# input_stage.net
KiCad netlist of a schematic drawn in EAGLE
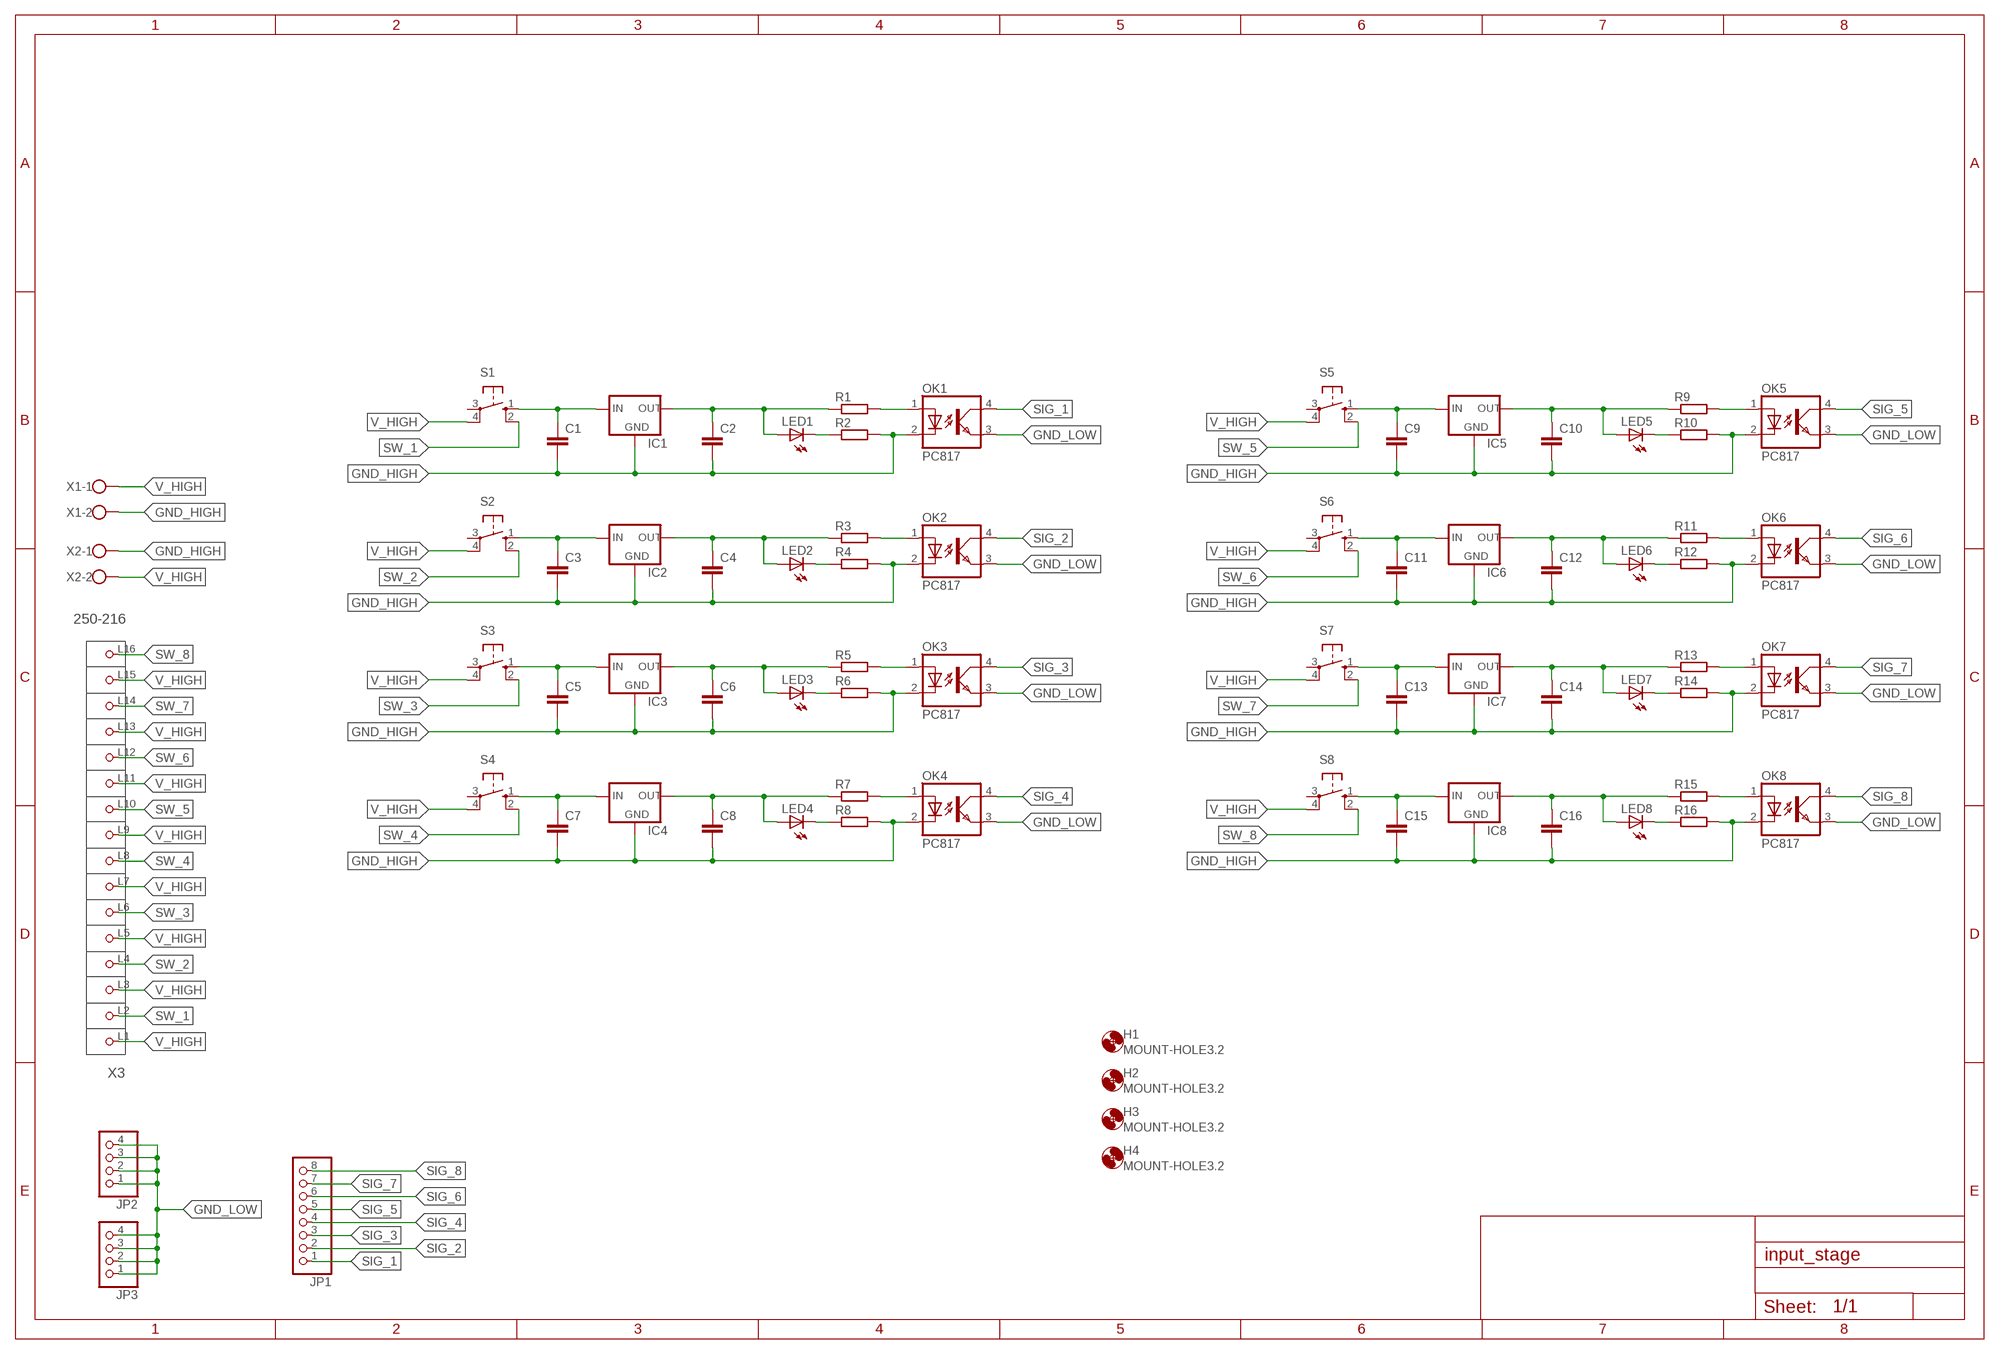
[diagram p0: schematic, sheet 1]

(export (version "E")
  (design (tool "Eeschema 10.0.6"))
  (components
    (comp (ref "C1")
      (value "C-EU050-024X044")
      (footprint "eagle-import:C050-024X044")
      (libsource (lib "eagle-import") (part "C-EU050-024X044"))
    )
    (comp (ref "C2")
      (value "C-EU050-024X044")
      (footprint "eagle-import:C050-024X044")
      (libsource (lib "eagle-import") (part "C-EU050-024X044"))
    )
    (comp (ref "C3")
      (value "C-EU050-024X044")
      (footprint "eagle-import:C050-024X044")
      (libsource (lib "eagle-import") (part "C-EU050-024X044"))
    )
    (comp (ref "C4")
      (value "C-EU050-024X044")
      (footprint "eagle-import:C050-024X044")
      (libsource (lib "eagle-import") (part "C-EU050-024X044"))
    )
    (comp (ref "C5")
      (value "C-EU050-024X044")
      (footprint "eagle-import:C050-024X044")
      (libsource (lib "eagle-import") (part "C-EU050-024X044"))
    )
    (comp (ref "C6")
      (value "C-EU050-024X044")
      (footprint "eagle-import:C050-024X044")
      (libsource (lib "eagle-import") (part "C-EU050-024X044"))
    )
    (comp (ref "C7")
      (value "C-EU050-024X044")
      (footprint "eagle-import:C050-024X044")
      (libsource (lib "eagle-import") (part "C-EU050-024X044"))
    )
    (comp (ref "C8")
      (value "C-EU050-024X044")
      (footprint "eagle-import:C050-024X044")
      (libsource (lib "eagle-import") (part "C-EU050-024X044"))
    )
    (comp (ref "C9")
      (value "C-EU050-024X044")
      (footprint "eagle-import:C050-024X044")
      (libsource (lib "eagle-import") (part "C-EU050-024X044"))
    )
    (comp (ref "C10")
      (value "C-EU050-024X044")
      (footprint "eagle-import:C050-024X044")
      (libsource (lib "eagle-import") (part "C-EU050-024X044"))
    )
    (comp (ref "C11")
      (value "C-EU050-024X044")
      (footprint "eagle-import:C050-024X044")
      (libsource (lib "eagle-import") (part "C-EU050-024X044"))
    )
    (comp (ref "C12")
      (value "C-EU050-024X044")
      (footprint "eagle-import:C050-024X044")
      (libsource (lib "eagle-import") (part "C-EU050-024X044"))
    )
    (comp (ref "C13")
      (value "C-EU050-024X044")
      (footprint "eagle-import:C050-024X044")
      (libsource (lib "eagle-import") (part "C-EU050-024X044"))
    )
    (comp (ref "C14")
      (value "C-EU050-024X044")
      (footprint "eagle-import:C050-024X044")
      (libsource (lib "eagle-import") (part "C-EU050-024X044"))
    )
    (comp (ref "C15")
      (value "C-EU050-024X044")
      (footprint "eagle-import:C050-024X044")
      (libsource (lib "eagle-import") (part "C-EU050-024X044"))
    )
    (comp (ref "C16")
      (value "C-EU050-024X044")
      (footprint "eagle-import:C050-024X044")
      (libsource (lib "eagle-import") (part "C-EU050-024X044"))
    )
    (comp (ref "H1")
      (value "MOUNT-HOLE3.2")
      (footprint "eagle-import:3,2")
      (libsource (lib "eagle-import") (part "MOUNT-HOLE3.2"))
    )
    (comp (ref "H2")
      (value "MOUNT-HOLE3.2")
      (footprint "eagle-import:3,2")
      (libsource (lib "eagle-import") (part "MOUNT-HOLE3.2"))
    )
    (comp (ref "H3")
      (value "MOUNT-HOLE3.2")
      (footprint "eagle-import:3,2")
      (libsource (lib "eagle-import") (part "MOUNT-HOLE3.2"))
    )
    (comp (ref "H4")
      (value "MOUNT-HOLE3.2")
      (footprint "eagle-import:3,2")
      (libsource (lib "eagle-import") (part "MOUNT-HOLE3.2"))
    )
    (comp (ref "IC1")
      (value "78LXX")
      (footprint "eagle-import:78LXX")
      (libsource (lib "eagle-import") (part "78LXX"))
    )
    (comp (ref "IC2")
      (value "78LXX")
      (footprint "eagle-import:78LXX")
      (libsource (lib "eagle-import") (part "78LXX"))
    )
    (comp (ref "IC3")
      (value "78LXX")
      (footprint "eagle-import:78LXX")
      (libsource (lib "eagle-import") (part "78LXX"))
    )
    (comp (ref "IC4")
      (value "78LXX")
      (footprint "eagle-import:78LXX")
      (libsource (lib "eagle-import") (part "78LXX"))
    )
    (comp (ref "IC5")
      (value "78LXX")
      (footprint "eagle-import:78LXX")
      (libsource (lib "eagle-import") (part "78LXX"))
    )
    (comp (ref "IC6")
      (value "78LXX")
      (footprint "eagle-import:78LXX")
      (libsource (lib "eagle-import") (part "78LXX"))
    )
    (comp (ref "IC7")
      (value "78LXX")
      (footprint "eagle-import:78LXX")
      (libsource (lib "eagle-import") (part "78LXX"))
    )
    (comp (ref "IC8")
      (value "78LXX")
      (footprint "eagle-import:78LXX")
      (libsource (lib "eagle-import") (part "78LXX"))
    )
    (comp (ref "JP1")
      (value "PINHD-1X8")
      (footprint "eagle-import:1X08")
      (libsource (lib "eagle-import") (part "PINHD-1X8"))
    )
    (comp (ref "JP2")
      (value "PINHD-1X4")
      (footprint "eagle-import:1X04")
      (libsource (lib "eagle-import") (part "PINHD-1X4"))
    )
    (comp (ref "JP3")
      (value "PINHD-1X4")
      (footprint "eagle-import:1X04")
      (libsource (lib "eagle-import") (part "PINHD-1X4"))
    )
    (comp (ref "LED1")
      (value "LED3MM")
      (footprint "eagle-import:LED3MM")
      (libsource (lib "eagle-import") (part "LED3MM"))
    )
    (comp (ref "LED2")
      (value "LED3MM")
      (footprint "eagle-import:LED3MM")
      (libsource (lib "eagle-import") (part "LED3MM"))
    )
    (comp (ref "LED3")
      (value "LED3MM")
      (footprint "eagle-import:LED3MM")
      (libsource (lib "eagle-import") (part "LED3MM"))
    )
    (comp (ref "LED4")
      (value "LED3MM")
      (footprint "eagle-import:LED3MM")
      (libsource (lib "eagle-import") (part "LED3MM"))
    )
    (comp (ref "LED5")
      (value "LED3MM")
      (footprint "eagle-import:LED3MM")
      (libsource (lib "eagle-import") (part "LED3MM"))
    )
    (comp (ref "LED6")
      (value "LED3MM")
      (footprint "eagle-import:LED3MM")
      (libsource (lib "eagle-import") (part "LED3MM"))
    )
    (comp (ref "LED7")
      (value "LED3MM")
      (footprint "eagle-import:LED3MM")
      (libsource (lib "eagle-import") (part "LED3MM"))
    )
    (comp (ref "LED8")
      (value "LED3MM")
      (footprint "eagle-import:LED3MM")
      (libsource (lib "eagle-import") (part "LED3MM"))
    )
    (comp (ref "OK1")
      (value "PC817")
      (footprint "eagle-import:DIL04")
      (fields (field (name "MPN") "PC817X4J000F"))
      (libsource (lib "eagle-import") (part "PC817"))
    )
    (comp (ref "OK2")
      (value "PC817")
      (footprint "eagle-import:DIL04")
      (fields (field (name "MPN") "PC817X4J000F"))
      (libsource (lib "eagle-import") (part "PC817"))
    )
    (comp (ref "OK3")
      (value "PC817")
      (footprint "eagle-import:DIL04")
      (fields (field (name "MPN") "PC817X4J000F"))
      (libsource (lib "eagle-import") (part "PC817"))
    )
    (comp (ref "OK4")
      (value "PC817")
      (footprint "eagle-import:DIL04")
      (fields (field (name "MPN") "PC817X4J000F"))
      (libsource (lib "eagle-import") (part "PC817"))
    )
    (comp (ref "OK5")
      (value "PC817")
      (footprint "eagle-import:DIL04")
      (fields (field (name "MPN") "PC817X4J000F"))
      (libsource (lib "eagle-import") (part "PC817"))
    )
    (comp (ref "OK6")
      (value "PC817")
      (footprint "eagle-import:DIL04")
      (fields (field (name "MPN") "PC817X4J000F"))
      (libsource (lib "eagle-import") (part "PC817"))
    )
    (comp (ref "OK7")
      (value "PC817")
      (footprint "eagle-import:DIL04")
      (fields (field (name "MPN") "PC817X4J000F"))
      (libsource (lib "eagle-import") (part "PC817"))
    )
    (comp (ref "OK8")
      (value "PC817")
      (footprint "eagle-import:DIL04")
      (fields (field (name "MPN") "PC817X4J000F"))
      (libsource (lib "eagle-import") (part "PC817"))
    )
    (comp (ref "R1")
      (value "R-EU_0207/10")
      (footprint "eagle-import:0207_10")
      (libsource (lib "eagle-import") (part "R-EU_0207/10"))
    )
    (comp (ref "R2")
      (value "R-EU_0207/10")
      (footprint "eagle-import:0207_10")
      (libsource (lib "eagle-import") (part "R-EU_0207/10"))
    )
    (comp (ref "R3")
      (value "R-EU_0207/10")
      (footprint "eagle-import:0207_10")
      (libsource (lib "eagle-import") (part "R-EU_0207/10"))
    )
    (comp (ref "R4")
      (value "R-EU_0207/10")
      (footprint "eagle-import:0207_10")
      (libsource (lib "eagle-import") (part "R-EU_0207/10"))
    )
    (comp (ref "R5")
      (value "R-EU_0207/10")
      (footprint "eagle-import:0207_10")
      (libsource (lib "eagle-import") (part "R-EU_0207/10"))
    )
    (comp (ref "R6")
      (value "R-EU_0207/10")
      (footprint "eagle-import:0207_10")
      (libsource (lib "eagle-import") (part "R-EU_0207/10"))
    )
    (comp (ref "R7")
      (value "R-EU_0207/10")
      (footprint "eagle-import:0207_10")
      (libsource (lib "eagle-import") (part "R-EU_0207/10"))
    )
    (comp (ref "R8")
      (value "R-EU_0207/10")
      (footprint "eagle-import:0207_10")
      (libsource (lib "eagle-import") (part "R-EU_0207/10"))
    )
    (comp (ref "R9")
      (value "R-EU_0207/10")
      (footprint "eagle-import:0207_10")
      (libsource (lib "eagle-import") (part "R-EU_0207/10"))
    )
    (comp (ref "R10")
      (value "R-EU_0207/10")
      (footprint "eagle-import:0207_10")
      (libsource (lib "eagle-import") (part "R-EU_0207/10"))
    )
    (comp (ref "R11")
      (value "R-EU_0207/10")
      (footprint "eagle-import:0207_10")
      (libsource (lib "eagle-import") (part "R-EU_0207/10"))
    )
    (comp (ref "R12")
      (value "R-EU_0207/10")
      (footprint "eagle-import:0207_10")
      (libsource (lib "eagle-import") (part "R-EU_0207/10"))
    )
    (comp (ref "R13")
      (value "R-EU_0207/10")
      (footprint "eagle-import:0207_10")
      (libsource (lib "eagle-import") (part "R-EU_0207/10"))
    )
    (comp (ref "R14")
      (value "R-EU_0207/10")
      (footprint "eagle-import:0207_10")
      (libsource (lib "eagle-import") (part "R-EU_0207/10"))
    )
    (comp (ref "R15")
      (value "R-EU_0207/10")
      (footprint "eagle-import:0207_10")
      (libsource (lib "eagle-import") (part "R-EU_0207/10"))
    )
    (comp (ref "R16")
      (value "R-EU_0207/10")
      (footprint "eagle-import:0207_10")
      (libsource (lib "eagle-import") (part "R-EU_0207/10"))
    )
    (comp (ref "S1")
      (value "10-XX")
      (footprint "eagle-import:B3F-10XX")
      (fields (field (name "MPN") "B3F-1000"))
      (libsource (lib "eagle-import") (part "10-XX"))
    )
    (comp (ref "S2")
      (value "10-XX")
      (footprint "eagle-import:B3F-10XX")
      (fields (field (name "MPN") "B3F-1000"))
      (libsource (lib "eagle-import") (part "10-XX"))
    )
    (comp (ref "S3")
      (value "10-XX")
      (footprint "eagle-import:B3F-10XX")
      (fields (field (name "MPN") "B3F-1000"))
      (libsource (lib "eagle-import") (part "10-XX"))
    )
    (comp (ref "S4")
      (value "10-XX")
      (footprint "eagle-import:B3F-10XX")
      (fields (field (name "MPN") "B3F-1000"))
      (libsource (lib "eagle-import") (part "10-XX"))
    )
    (comp (ref "S5")
      (value "10-XX")
      (footprint "eagle-import:B3F-10XX")
      (fields (field (name "MPN") "B3F-1000"))
      (libsource (lib "eagle-import") (part "10-XX"))
    )
    (comp (ref "S6")
      (value "10-XX")
      (footprint "eagle-import:B3F-10XX")
      (fields (field (name "MPN") "B3F-1000"))
      (libsource (lib "eagle-import") (part "10-XX"))
    )
    (comp (ref "S7")
      (value "10-XX")
      (footprint "eagle-import:B3F-10XX")
      (fields (field (name "MPN") "B3F-1000"))
      (libsource (lib "eagle-import") (part "10-XX"))
    )
    (comp (ref "S8")
      (value "10-XX")
      (footprint "eagle-import:B3F-10XX")
      (fields (field (name "MPN") "B3F-1000"))
      (libsource (lib "eagle-import") (part "10-XX"))
    )
    (comp (ref "X1")
      (value "W237-102")
      (footprint "eagle-import:W237-102")
      (fields (field (name "MPN") "237-102"))
      (libsource (lib "eagle-import") (part "W237-102"))
    )
    (comp (ref "X2")
      (value "W237-102")
      (footprint "eagle-import:W237-102")
      (fields (field (name "MPN") "237-102"))
      (libsource (lib "eagle-import") (part "W237-102"))
    )
    (comp (ref "X3")
      (value "250-216")
      (footprint "eagle-import:P-250-216")
      (libsource (lib "eagle-import") (part "250-216"))
    )
  )
  (nets
    (net (code "1") (name "GND_HIGH") (class "Default")
      (node (ref "C1") (pin "2") (pinfunction "2_2") (pintype "passive"))
      (node (ref "C10") (pin "2") (pinfunction "2_2") (pintype "passive"))
      (node (ref "C11") (pin "2") (pinfunction "2_2") (pintype "passive"))
      (node (ref "C12") (pin "2") (pinfunction "2_2") (pintype "passive"))
      (node (ref "C13") (pin "2") (pinfunction "2_2") (pintype "passive"))
      (node (ref "C14") (pin "2") (pinfunction "2_2") (pintype "passive"))
      (node (ref "C15") (pin "2") (pinfunction "2_2") (pintype "passive"))
      (node (ref "C16") (pin "2") (pinfunction "2_2") (pintype "passive"))
      (node (ref "C2") (pin "2") (pinfunction "2_2") (pintype "passive"))
      (node (ref "C3") (pin "2") (pinfunction "2_2") (pintype "passive"))
      (node (ref "C4") (pin "2") (pinfunction "2_2") (pintype "passive"))
      (node (ref "C5") (pin "2") (pinfunction "2_2") (pintype "passive"))
      (node (ref "C6") (pin "2") (pinfunction "2_2") (pintype "passive"))
      (node (ref "C7") (pin "2") (pinfunction "2_2") (pintype "passive"))
      (node (ref "C8") (pin "2") (pinfunction "2_2") (pintype "passive"))
      (node (ref "C9") (pin "2") (pinfunction "2_2") (pintype "passive"))
      (node (ref "IC1") (pin "GND") (pinfunction "GND_GND") (pintype "input"))
      (node (ref "IC2") (pin "GND") (pinfunction "GND_GND") (pintype "input"))
      (node (ref "IC3") (pin "GND") (pinfunction "GND_GND") (pintype "input"))
      (node (ref "IC4") (pin "GND") (pinfunction "GND_GND") (pintype "input"))
      (node (ref "IC5") (pin "GND") (pinfunction "GND_GND") (pintype "input"))
      (node (ref "IC6") (pin "GND") (pinfunction "GND_GND") (pintype "input"))
      (node (ref "IC7") (pin "GND") (pinfunction "GND_GND") (pintype "input"))
      (node (ref "IC8") (pin "GND") (pinfunction "GND_GND") (pintype "input"))
      (node (ref "OK1") (pin "2") (pinfunction "C_2") (pintype "passive"))
      (node (ref "OK2") (pin "2") (pinfunction "C_2") (pintype "passive"))
      (node (ref "OK3") (pin "2") (pinfunction "C_2") (pintype "passive"))
      (node (ref "OK4") (pin "2") (pinfunction "C_2") (pintype "passive"))
      (node (ref "OK5") (pin "2") (pinfunction "C_2") (pintype "passive"))
      (node (ref "OK6") (pin "2") (pinfunction "C_2") (pintype "passive"))
      (node (ref "OK7") (pin "2") (pinfunction "C_2") (pintype "passive"))
      (node (ref "OK8") (pin "2") (pinfunction "C_2") (pintype "passive"))
      (node (ref "R10") (pin "2") (pinfunction "2_2") (pintype "passive"))
      (node (ref "R12") (pin "2") (pinfunction "2_2") (pintype "passive"))
      (node (ref "R14") (pin "2") (pinfunction "2_2") (pintype "passive"))
      (node (ref "R16") (pin "2") (pinfunction "2_2") (pintype "passive"))
      (node (ref "R2") (pin "2") (pinfunction "2_2") (pintype "passive"))
      (node (ref "R4") (pin "2") (pinfunction "2_2") (pintype "passive"))
      (node (ref "R6") (pin "2") (pinfunction "2_2") (pintype "passive"))
      (node (ref "R8") (pin "2") (pinfunction "2_2") (pintype "passive"))
      (node (ref "X1") (pin "2") (pinfunction "KL_2") (pintype "passive"))
      (node (ref "X2") (pin "1") (pinfunction "KL_1") (pintype "passive"))
    )
    (net (code "2") (name "GND_LOW") (class "Default")
      (node (ref "JP2") (pin "1") (pinfunction "1_1") (pintype "passive"))
      (node (ref "JP2") (pin "2") (pinfunction "2_2") (pintype "passive"))
      (node (ref "JP2") (pin "3") (pinfunction "3_3") (pintype "passive"))
      (node (ref "JP2") (pin "4") (pinfunction "4_4") (pintype "passive"))
      (node (ref "JP3") (pin "1") (pinfunction "1_1") (pintype "passive"))
      (node (ref "JP3") (pin "2") (pinfunction "2_2") (pintype "passive"))
      (node (ref "JP3") (pin "3") (pinfunction "3_3") (pintype "passive"))
      (node (ref "JP3") (pin "4") (pinfunction "4_4") (pintype "passive"))
      (node (ref "OK1") (pin "3") (pinfunction "EMIT_3") (pintype "passive"))
      (node (ref "OK2") (pin "3") (pinfunction "EMIT_3") (pintype "passive"))
      (node (ref "OK3") (pin "3") (pinfunction "EMIT_3") (pintype "passive"))
      (node (ref "OK4") (pin "3") (pinfunction "EMIT_3") (pintype "passive"))
      (node (ref "OK5") (pin "3") (pinfunction "EMIT_3") (pintype "passive"))
      (node (ref "OK6") (pin "3") (pinfunction "EMIT_3") (pintype "passive"))
      (node (ref "OK7") (pin "3") (pinfunction "EMIT_3") (pintype "passive"))
      (node (ref "OK8") (pin "3") (pinfunction "EMIT_3") (pintype "passive"))
    )
    (net (code "3") (name "Net-(C2-Pad1)") (class "Default")
      (node (ref "C2") (pin "1") (pinfunction "1_1") (pintype "passive"))
      (node (ref "IC1") (pin "OUT") (pinfunction "OUT_OUT") (pintype "passive"))
      (node (ref "LED1") (pin "A") (pinfunction "A_A") (pintype "passive"))
      (node (ref "R1") (pin "1") (pinfunction "1_1") (pintype "passive"))
    )
    (net (code "4") (name "Net-(C4-Pad1)") (class "Default")
      (node (ref "C4") (pin "1") (pinfunction "1_1") (pintype "passive"))
      (node (ref "IC2") (pin "OUT") (pinfunction "OUT_OUT") (pintype "passive"))
      (node (ref "LED2") (pin "A") (pinfunction "A_A") (pintype "passive"))
      (node (ref "R3") (pin "1") (pinfunction "1_1") (pintype "passive"))
    )
    (net (code "5") (name "Net-(C6-Pad1)") (class "Default")
      (node (ref "C6") (pin "1") (pinfunction "1_1") (pintype "passive"))
      (node (ref "IC3") (pin "OUT") (pinfunction "OUT_OUT") (pintype "passive"))
      (node (ref "LED3") (pin "A") (pinfunction "A_A") (pintype "passive"))
      (node (ref "R5") (pin "1") (pinfunction "1_1") (pintype "passive"))
    )
    (net (code "6") (name "Net-(C8-Pad1)") (class "Default")
      (node (ref "C8") (pin "1") (pinfunction "1_1") (pintype "passive"))
      (node (ref "IC4") (pin "OUT") (pinfunction "OUT_OUT") (pintype "passive"))
      (node (ref "LED4") (pin "A") (pinfunction "A_A") (pintype "passive"))
      (node (ref "R7") (pin "1") (pinfunction "1_1") (pintype "passive"))
    )
    (net (code "7") (name "Net-(C10-Pad1)") (class "Default")
      (node (ref "C10") (pin "1") (pinfunction "1_1") (pintype "passive"))
      (node (ref "IC5") (pin "OUT") (pinfunction "OUT_OUT") (pintype "passive"))
      (node (ref "LED5") (pin "A") (pinfunction "A_A") (pintype "passive"))
      (node (ref "R9") (pin "1") (pinfunction "1_1") (pintype "passive"))
    )
    (net (code "8") (name "Net-(C12-Pad1)") (class "Default")
      (node (ref "C12") (pin "1") (pinfunction "1_1") (pintype "passive"))
      (node (ref "IC6") (pin "OUT") (pinfunction "OUT_OUT") (pintype "passive"))
      (node (ref "LED6") (pin "A") (pinfunction "A_A") (pintype "passive"))
      (node (ref "R11") (pin "1") (pinfunction "1_1") (pintype "passive"))
    )
    (net (code "9") (name "Net-(C14-Pad1)") (class "Default")
      (node (ref "C14") (pin "1") (pinfunction "1_1") (pintype "passive"))
      (node (ref "IC7") (pin "OUT") (pinfunction "OUT_OUT") (pintype "passive"))
      (node (ref "LED7") (pin "A") (pinfunction "A_A") (pintype "passive"))
      (node (ref "R13") (pin "1") (pinfunction "1_1") (pintype "passive"))
    )
    (net (code "10") (name "Net-(C16-Pad1)") (class "Default")
      (node (ref "C16") (pin "1") (pinfunction "1_1") (pintype "passive"))
      (node (ref "IC8") (pin "OUT") (pinfunction "OUT_OUT") (pintype "passive"))
      (node (ref "LED8") (pin "A") (pinfunction "A_A") (pintype "passive"))
      (node (ref "R15") (pin "1") (pinfunction "1_1") (pintype "passive"))
    )
    (net (code "11") (name "Net-(LED1-C)") (class "Default")
      (node (ref "LED1") (pin "K") (pinfunction "C_K") (pintype "passive"))
      (node (ref "R2") (pin "1") (pinfunction "1_1") (pintype "passive"))
    )
    (net (code "12") (name "Net-(LED2-C)") (class "Default")
      (node (ref "LED2") (pin "K") (pinfunction "C_K") (pintype "passive"))
      (node (ref "R4") (pin "1") (pinfunction "1_1") (pintype "passive"))
    )
    (net (code "13") (name "Net-(LED3-C)") (class "Default")
      (node (ref "LED3") (pin "K") (pinfunction "C_K") (pintype "passive"))
      (node (ref "R6") (pin "1") (pinfunction "1_1") (pintype "passive"))
    )
    (net (code "14") (name "Net-(LED4-C)") (class "Default")
      (node (ref "LED4") (pin "K") (pinfunction "C_K") (pintype "passive"))
      (node (ref "R8") (pin "1") (pinfunction "1_1") (pintype "passive"))
    )
    (net (code "15") (name "Net-(LED5-C)") (class "Default")
      (node (ref "LED5") (pin "K") (pinfunction "C_K") (pintype "passive"))
      (node (ref "R10") (pin "1") (pinfunction "1_1") (pintype "passive"))
    )
    (net (code "16") (name "Net-(LED6-C)") (class "Default")
      (node (ref "LED6") (pin "K") (pinfunction "C_K") (pintype "passive"))
      (node (ref "R12") (pin "1") (pinfunction "1_1") (pintype "passive"))
    )
    (net (code "17") (name "Net-(LED7-C)") (class "Default")
      (node (ref "LED7") (pin "K") (pinfunction "C_K") (pintype "passive"))
      (node (ref "R14") (pin "1") (pinfunction "1_1") (pintype "passive"))
    )
    (net (code "18") (name "Net-(LED8-C)") (class "Default")
      (node (ref "LED8") (pin "K") (pinfunction "C_K") (pintype "passive"))
      (node (ref "R16") (pin "1") (pinfunction "1_1") (pintype "passive"))
    )
    (net (code "19") (name "Net-(OK1-A)") (class "Default")
      (node (ref "OK1") (pin "1") (pinfunction "A_1") (pintype "passive"))
      (node (ref "R1") (pin "2") (pinfunction "2_2") (pintype "passive"))
    )
    (net (code "20") (name "Net-(OK2-A)") (class "Default")
      (node (ref "OK2") (pin "1") (pinfunction "A_1") (pintype "passive"))
      (node (ref "R3") (pin "2") (pinfunction "2_2") (pintype "passive"))
    )
    (net (code "21") (name "Net-(OK3-A)") (class "Default")
      (node (ref "OK3") (pin "1") (pinfunction "A_1") (pintype "passive"))
      (node (ref "R5") (pin "2") (pinfunction "2_2") (pintype "passive"))
    )
    (net (code "22") (name "Net-(OK4-A)") (class "Default")
      (node (ref "OK4") (pin "1") (pinfunction "A_1") (pintype "passive"))
      (node (ref "R7") (pin "2") (pinfunction "2_2") (pintype "passive"))
    )
    (net (code "23") (name "Net-(OK5-A)") (class "Default")
      (node (ref "OK5") (pin "1") (pinfunction "A_1") (pintype "passive"))
      (node (ref "R9") (pin "2") (pinfunction "2_2") (pintype "passive"))
    )
    (net (code "24") (name "Net-(OK6-A)") (class "Default")
      (node (ref "OK6") (pin "1") (pinfunction "A_1") (pintype "passive"))
      (node (ref "R11") (pin "2") (pinfunction "2_2") (pintype "passive"))
    )
    (net (code "25") (name "Net-(OK7-A)") (class "Default")
      (node (ref "OK7") (pin "1") (pinfunction "A_1") (pintype "passive"))
      (node (ref "R13") (pin "2") (pinfunction "2_2") (pintype "passive"))
    )
    (net (code "26") (name "Net-(OK8-A)") (class "Default")
      (node (ref "OK8") (pin "1") (pinfunction "A_1") (pintype "passive"))
      (node (ref "R15") (pin "2") (pinfunction "2_2") (pintype "passive"))
    )
    (net (code "27") (name "Net-(S1-S)") (class "Default")
      (node (ref "C1") (pin "1") (pinfunction "1_1") (pintype "passive"))
      (node (ref "IC1") (pin "IN") (pinfunction "IN_IN") (pintype "input"))
      (node (ref "S1") (pin "1") (pinfunction "S_1") (pintype "passive"))
    )
    (net (code "28") (name "Net-(S2-S)") (class "Default")
      (node (ref "C3") (pin "1") (pinfunction "1_1") (pintype "passive"))
      (node (ref "IC2") (pin "IN") (pinfunction "IN_IN") (pintype "input"))
      (node (ref "S2") (pin "1") (pinfunction "S_1") (pintype "passive"))
    )
    (net (code "29") (name "Net-(S3-S)") (class "Default")
      (node (ref "C5") (pin "1") (pinfunction "1_1") (pintype "passive"))
      (node (ref "IC3") (pin "IN") (pinfunction "IN_IN") (pintype "input"))
      (node (ref "S3") (pin "1") (pinfunction "S_1") (pintype "passive"))
    )
    (net (code "30") (name "Net-(S4-S)") (class "Default")
      (node (ref "C7") (pin "1") (pinfunction "1_1") (pintype "passive"))
      (node (ref "IC4") (pin "IN") (pinfunction "IN_IN") (pintype "input"))
      (node (ref "S4") (pin "1") (pinfunction "S_1") (pintype "passive"))
    )
    (net (code "31") (name "Net-(S5-S)") (class "Default")
      (node (ref "C9") (pin "1") (pinfunction "1_1") (pintype "passive"))
      (node (ref "IC5") (pin "IN") (pinfunction "IN_IN") (pintype "input"))
      (node (ref "S5") (pin "1") (pinfunction "S_1") (pintype "passive"))
    )
    (net (code "32") (name "Net-(S6-S)") (class "Default")
      (node (ref "C11") (pin "1") (pinfunction "1_1") (pintype "passive"))
      (node (ref "IC6") (pin "IN") (pinfunction "IN_IN") (pintype "input"))
      (node (ref "S6") (pin "1") (pinfunction "S_1") (pintype "passive"))
    )
    (net (code "33") (name "Net-(S7-S)") (class "Default")
      (node (ref "C13") (pin "1") (pinfunction "1_1") (pintype "passive"))
      (node (ref "IC7") (pin "IN") (pinfunction "IN_IN") (pintype "input"))
      (node (ref "S7") (pin "1") (pinfunction "S_1") (pintype "passive"))
    )
    (net (code "34") (name "Net-(S8-S)") (class "Default")
      (node (ref "C15") (pin "1") (pinfunction "1_1") (pintype "passive"))
      (node (ref "IC8") (pin "IN") (pinfunction "IN_IN") (pintype "input"))
      (node (ref "S8") (pin "1") (pinfunction "S_1") (pintype "passive"))
    )
    (net (code "35") (name "SIG_1") (class "Default")
      (node (ref "JP1") (pin "1") (pinfunction "1_1") (pintype "passive"))
      (node (ref "OK1") (pin "4") (pinfunction "COL_4") (pintype "passive"))
    )
    (net (code "36") (name "SIG_2") (class "Default")
      (node (ref "JP1") (pin "2") (pinfunction "2_2") (pintype "passive"))
      (node (ref "OK2") (pin "4") (pinfunction "COL_4") (pintype "passive"))
    )
    (net (code "37") (name "SIG_3") (class "Default")
      (node (ref "JP1") (pin "3") (pinfunction "3_3") (pintype "passive"))
      (node (ref "OK3") (pin "4") (pinfunction "COL_4") (pintype "passive"))
    )
    (net (code "38") (name "SIG_4") (class "Default")
      (node (ref "JP1") (pin "4") (pinfunction "4_4") (pintype "passive"))
      (node (ref "OK4") (pin "4") (pinfunction "COL_4") (pintype "passive"))
    )
    (net (code "39") (name "SIG_5") (class "Default")
      (node (ref "JP1") (pin "5") (pinfunction "5_5") (pintype "passive"))
      (node (ref "OK5") (pin "4") (pinfunction "COL_4") (pintype "passive"))
    )
    (net (code "40") (name "SIG_6") (class "Default")
      (node (ref "JP1") (pin "6") (pinfunction "6_6") (pintype "passive"))
      (node (ref "OK6") (pin "4") (pinfunction "COL_4") (pintype "passive"))
    )
    (net (code "41") (name "SIG_7") (class "Default")
      (node (ref "JP1") (pin "7") (pinfunction "7_7") (pintype "passive"))
      (node (ref "OK7") (pin "4") (pinfunction "COL_4") (pintype "passive"))
    )
    (net (code "42") (name "SIG_8") (class "Default")
      (node (ref "JP1") (pin "8") (pinfunction "8_8") (pintype "passive"))
      (node (ref "OK8") (pin "4") (pinfunction "COL_4") (pintype "passive"))
    )
    (net (code "43") (name "SW_1") (class "Default")
      (node (ref "S1") (pin "2") (pinfunction "S1_2") (pintype "passive"))
      (node (ref "X3") (pin "L2") (pinfunction "P2_L2") (pintype "bidirectional"))
    )
    (net (code "44") (name "SW_2") (class "Default")
      (node (ref "S2") (pin "2") (pinfunction "S1_2") (pintype "passive"))
      (node (ref "X3") (pin "L4") (pinfunction "P4_L4") (pintype "bidirectional"))
    )
    (net (code "45") (name "SW_3") (class "Default")
      (node (ref "S3") (pin "2") (pinfunction "S1_2") (pintype "passive"))
      (node (ref "X3") (pin "L6") (pinfunction "P6_L6") (pintype "bidirectional"))
    )
    (net (code "46") (name "SW_4") (class "Default")
      (node (ref "S4") (pin "2") (pinfunction "S1_2") (pintype "passive"))
      (node (ref "X3") (pin "L8") (pinfunction "P8_L8") (pintype "bidirectional"))
    )
    (net (code "47") (name "SW_5") (class "Default")
      (node (ref "S5") (pin "2") (pinfunction "S1_2") (pintype "passive"))
      (node (ref "X3") (pin "L10") (pinfunction "P10_L10") (pintype "bidirectional"))
    )
    (net (code "48") (name "SW_6") (class "Default")
      (node (ref "S6") (pin "2") (pinfunction "S1_2") (pintype "passive"))
      (node (ref "X3") (pin "L12") (pinfunction "P12_L12") (pintype "bidirectional"))
    )
    (net (code "49") (name "SW_7") (class "Default")
      (node (ref "S7") (pin "2") (pinfunction "S1_2") (pintype "passive"))
      (node (ref "X3") (pin "L14") (pinfunction "P14_L14") (pintype "bidirectional"))
    )
    (net (code "50") (name "SW_8") (class "Default")
      (node (ref "S8") (pin "2") (pinfunction "S1_2") (pintype "passive"))
      (node (ref "X3") (pin "L16") (pinfunction "P16_L16") (pintype "bidirectional"))
    )
    (net (code "51") (name "V_HIGH") (class "Default")
      (node (ref "S1") (pin "4") (pinfunction "P1_4") (pintype "passive"))
      (node (ref "S2") (pin "4") (pinfunction "P1_4") (pintype "passive"))
      (node (ref "S3") (pin "4") (pinfunction "P1_4") (pintype "passive"))
      (node (ref "S4") (pin "4") (pinfunction "P1_4") (pintype "passive"))
      (node (ref "S5") (pin "4") (pinfunction "P1_4") (pintype "passive"))
      (node (ref "S6") (pin "4") (pinfunction "P1_4") (pintype "passive"))
      (node (ref "S7") (pin "4") (pinfunction "P1_4") (pintype "passive"))
      (node (ref "S8") (pin "4") (pinfunction "P1_4") (pintype "passive"))
      (node (ref "X1") (pin "1") (pinfunction "KL_1") (pintype "passive"))
      (node (ref "X2") (pin "2") (pinfunction "KL_2") (pintype "passive"))
      (node (ref "X3") (pin "L1") (pinfunction "P1_L1") (pintype "bidirectional"))
      (node (ref "X3") (pin "L11") (pinfunction "P11_L11") (pintype "bidirectional"))
      (node (ref "X3") (pin "L13") (pinfunction "P13_L13") (pintype "bidirectional"))
      (node (ref "X3") (pin "L15") (pinfunction "P15_L15") (pintype "bidirectional"))
      (node (ref "X3") (pin "L3") (pinfunction "P3_L3") (pintype "bidirectional"))
      (node (ref "X3") (pin "L5") (pinfunction "P5_L5") (pintype "bidirectional"))
      (node (ref "X3") (pin "L7") (pinfunction "P7_L7") (pintype "bidirectional"))
      (node (ref "X3") (pin "L9") (pinfunction "P9_L9") (pintype "bidirectional"))
    )
    (net (code "52") (name "unconnected-(S1-P-Pad3)") (class "Default")
      (node (ref "S1") (pin "3") (pinfunction "P_3") (pintype "passive"))
    )
    (net (code "53") (name "unconnected-(S2-P-Pad3)") (class "Default")
      (node (ref "S2") (pin "3") (pinfunction "P_3") (pintype "passive"))
    )
    (net (code "54") (name "unconnected-(S3-P-Pad3)") (class "Default")
      (node (ref "S3") (pin "3") (pinfunction "P_3") (pintype "passive"))
    )
    (net (code "55") (name "unconnected-(S4-P-Pad3)") (class "Default")
      (node (ref "S4") (pin "3") (pinfunction "P_3") (pintype "passive"))
    )
    (net (code "56") (name "unconnected-(S5-P-Pad3)") (class "Default")
      (node (ref "S5") (pin "3") (pinfunction "P_3") (pintype "passive"))
    )
    (net (code "57") (name "unconnected-(S6-P-Pad3)") (class "Default")
      (node (ref "S6") (pin "3") (pinfunction "P_3") (pintype "passive"))
    )
    (net (code "58") (name "unconnected-(S7-P-Pad3)") (class "Default")
      (node (ref "S7") (pin "3") (pinfunction "P_3") (pintype "passive"))
    )
    (net (code "59") (name "unconnected-(S8-P-Pad3)") (class "Default")
      (node (ref "S8") (pin "3") (pinfunction "P_3") (pintype "passive"))
    )
  )
)
